# uController.net
KiCad netlist of a schematic drawn in Altium Designer
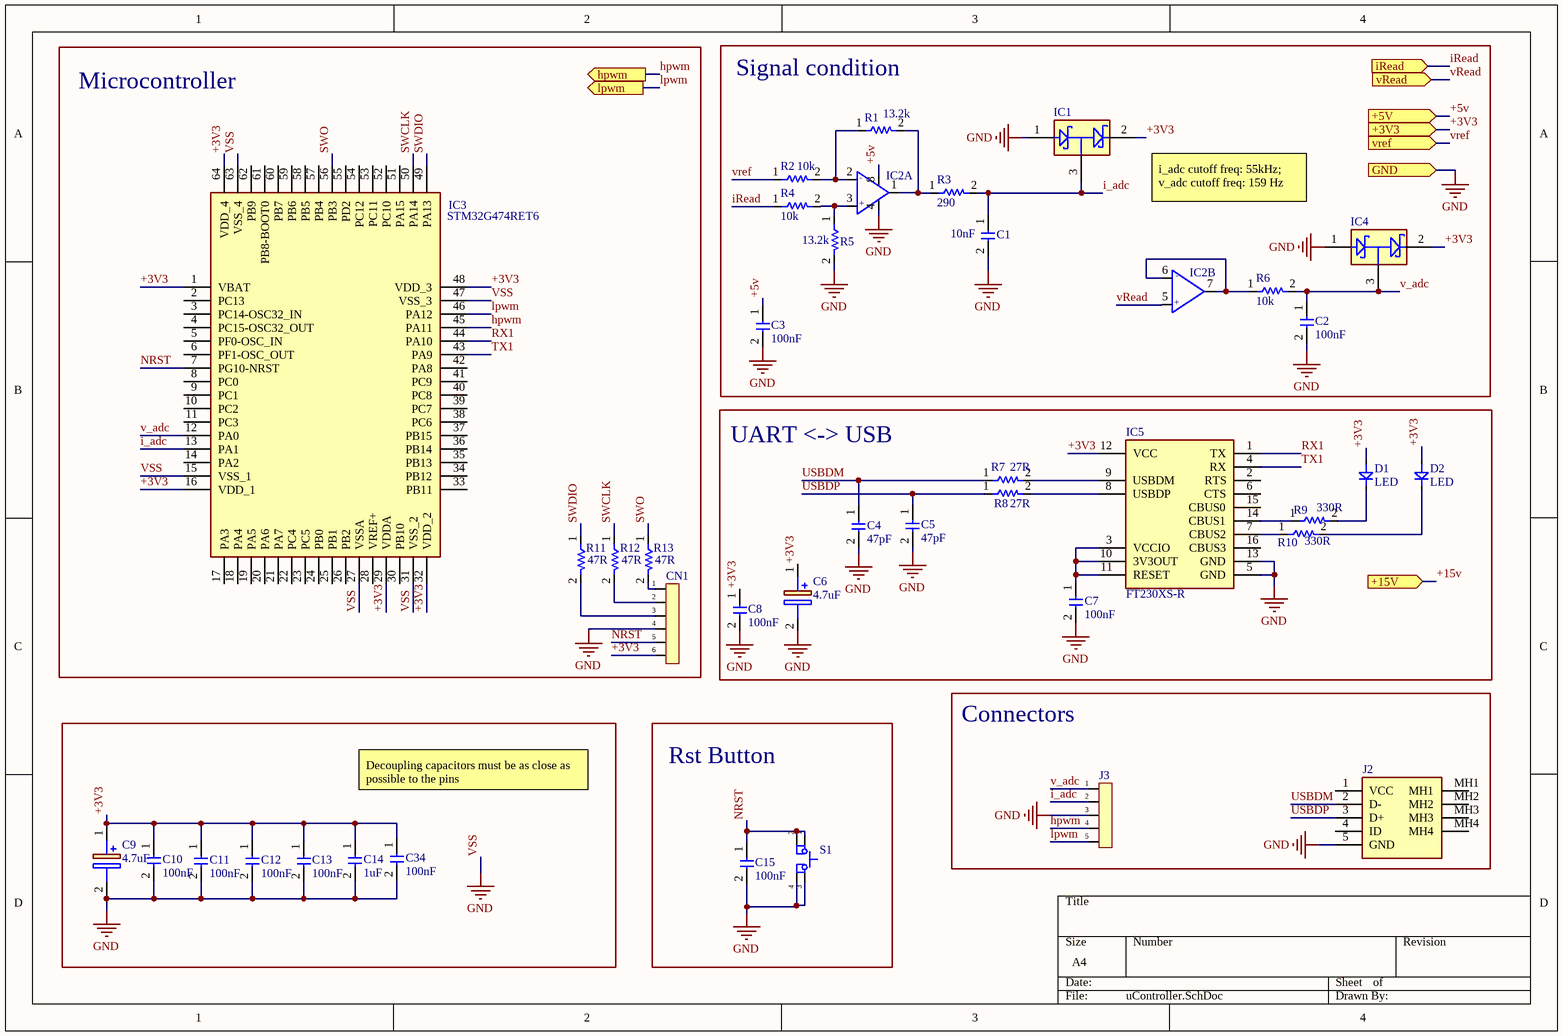
[diagram p0: uController.SchDoc]

(export (version "E")
  (design (tool "Eeschema 10.0.6"))
  (components
    (comp (ref "C1")
      (value "10nF")
      (footprint "CAPACITOR_0805")
      (libsource (lib "Schlib1") (part "Capacitor"))
    )
    (comp (ref "C2")
      (value "100nF")
      (footprint "CAPACITOR_0805")
      (libsource (lib "Schlib1") (part "Capacitor"))
    )
    (comp (ref "C3")
      (value "100nF")
      (footprint "CAPACITOR_0805")
      (libsource (lib "Schlib1") (part "Capacitor"))
    )
    (comp (ref "C4")
      (value "47pF")
      (footprint "CAPACITOR_0805")
      (libsource (lib "Schlib1") (part "Capacitor"))
    )
    (comp (ref "C5")
      (value "47pF")
      (footprint "CAPACITOR_0805")
      (libsource (lib "Schlib1") (part "Capacitor"))
    )
    (comp (ref "C6")
      (value "4.7uF")
      (footprint "Capacitor 0805 polaryzed")
      (libsource (lib "Schlib1") (part "Capacitor polaryzed"))
    )
    (comp (ref "C7")
      (value "100nF")
      (footprint "CAPACITOR_0805")
      (libsource (lib "Schlib1") (part "Capacitor"))
    )
    (comp (ref "C8")
      (value "100nF")
      (footprint "CAPACITOR_0805")
      (libsource (lib "Schlib1") (part "Capacitor"))
    )
    (comp (ref "C9")
      (value "4.7uF")
      (footprint "Capacitor 0805 polaryzed")
      (libsource (lib "Schlib1") (part "Capacitor polaryzed"))
    )
    (comp (ref "C10")
      (value "100nF")
      (footprint "CAPACITOR_0805")
      (libsource (lib "Schlib1") (part "Capacitor"))
    )
    (comp (ref "C11")
      (value "100nF")
      (footprint "CAPACITOR_0805")
      (libsource (lib "Schlib1") (part "Capacitor"))
    )
    (comp (ref "C12")
      (value "100nF")
      (footprint "CAPACITOR_0805")
      (libsource (lib "Schlib1") (part "Capacitor"))
    )
    (comp (ref "C13")
      (value "100nF")
      (footprint "CAPACITOR_0805")
      (libsource (lib "Schlib1") (part "Capacitor"))
    )
    (comp (ref "C14")
      (value "1uF")
      (footprint "CAPACITOR_0805")
      (libsource (lib "Schlib1") (part "Capacitor"))
    )
    (comp (ref "C15")
      (value "100nF")
      (footprint "CAPACITOR_0805")
      (libsource (lib "Schlib1") (part "Capacitor"))
    )
    (comp (ref "C34")
      (value "100nF")
      (footprint "CAPACITOR_0805")
      (libsource (lib "Schlib1") (part "Capacitor"))
    )
    (comp (ref "CN1")
      (value "Conector 1x6P")
      (footprint "Header 2x3")
      (libsource (lib "Schlib1") (part "Conector 1x6P"))
    )
    (comp (ref "D1") (value "LED") (footprint "LED 0805") (libsource (lib "Schlib1") (part "LED")))
    (comp (ref "D2") (value "LED") (footprint "LED 0805") (libsource (lib "Schlib1") (part "LED")))
    (comp (ref "IC1") (value "bat54s") (footprint "BAT54S") (libsource (lib "Schlib1") (part "bat54s")))
    (comp (ref "IC2") (value "TSX712IDT") (footprint "SO-8") (libsource (lib "Schlib1") (part "TSX712IDT")))
    (comp (ref "IC3")
      (value "STM32G474RET6")
      (footprint "QFP50P1200X1200X160-64N")
      (description "Integrated Circuit")
      (fields (field (name "MOUSER PART NUMBER") "511-STM32G474RET6"))
      (libsource (lib "*") (part "STM32G474RET6"))
    )
    (comp (ref "IC4") (value "bat54s") (footprint "BAT54S") (libsource (lib "Schlib1") (part "bat54s")))
    (comp (ref "IC5")
      (value "FT230XS-R")
      (footprint "SSOP-16")
      (libsource (lib "Schlib1") (part "FT230XS-R"))
    )
    (comp (ref "J2")
      (value "UJ2-MIBH2-4-SMT-TR")
      (footprint "UJ2MIBH24SMTTR")
      (description "Connector")
      (fields (field (name "MOUSER PART NUMBER") "490-UJ2-MIBH2-4-SMT"))
      (libsource (lib "Schlib1") (part "UJ2-MIBH2-4-SMT-TR"))
    )
    (comp (ref "J3")
      (value "Conector 1x5P")
      (footprint "HEADER 1X5")
      (libsource (lib "Schlib1") (part "Conector 1x5P"))
    )
    (comp (ref "R1")
      (value "13.2k")
      (footprint "RESISTOR_0805")
      (libsource (lib "Schlib1") (part "Resistor"))
    )
    (comp (ref "R2") (value "10k") (footprint "RESISTOR_0805") (libsource (lib "Schlib1") (part "Resistor")))
    (comp (ref "R3") (value "290") (footprint "RESISTOR_0805") (libsource (lib "Schlib1") (part "Resistor")))
    (comp (ref "R4") (value "10k") (footprint "RESISTOR_0805") (libsource (lib "Schlib1") (part "Resistor")))
    (comp (ref "R5")
      (value "13.2k")
      (footprint "RESISTOR_0805")
      (libsource (lib "Schlib1") (part "Resistor"))
    )
    (comp (ref "R6") (value "10k") (footprint "RESISTOR_0805") (libsource (lib "Schlib1") (part "Resistor")))
    (comp (ref "R7") (value "27R") (footprint "RESISTOR_0805") (libsource (lib "Schlib1") (part "Resistor")))
    (comp (ref "R8") (value "27R") (footprint "RESISTOR_0805") (libsource (lib "Schlib1") (part "Resistor")))
    (comp (ref "R9") (value "330R") (footprint "RESISTOR_0805") (libsource (lib "Schlib1") (part "Resistor")))
    (comp (ref "R10")
      (value "330R")
      (footprint "RESISTOR_0805")
      (libsource (lib "Schlib1") (part "Resistor"))
    )
    (comp (ref "R11") (value "47R") (footprint "RESISTOR_0805") (libsource (lib "Schlib1") (part "Resistor")))
    (comp (ref "R12") (value "47R") (footprint "RESISTOR_0805") (libsource (lib "Schlib1") (part "Resistor")))
    (comp (ref "R13") (value "47R") (footprint "RESISTOR_0805") (libsource (lib "Schlib1") (part "Resistor")))
    (comp (ref "S1")
      (value "pushButton")
      (footprint "Push_Button")
      (libsource (lib "Schlib1") (part "pushButton"))
    )
  )
  (nets
    (net (code "1") (name "/+3V3") (class "Default")
      (node (ref "C10") (pin "1") (pinfunction "1_1") (pintype "passive"))
      (node (ref "C11") (pin "1") (pinfunction "1_1") (pintype "passive"))
      (node (ref "C12") (pin "1") (pinfunction "1_1") (pintype "passive"))
      (node (ref "C13") (pin "1") (pinfunction "1_1") (pintype "passive"))
      (node (ref "C14") (pin "1") (pinfunction "1_1") (pintype "passive"))
      (node (ref "C34") (pin "1") (pinfunction "1_1") (pintype "passive"))
      (node (ref "C6") (pin "1") (pinfunction "+_1") (pintype "passive"))
      (node (ref "C8") (pin "1") (pinfunction "1_1") (pintype "passive"))
      (node (ref "C9") (pin "1") (pinfunction "+_1") (pintype "passive"))
      (node (ref "CN1") (pin "6") (pinfunction "6_6") (pintype "passive"))
      (node (ref "D1") (pin "2") (pinfunction "12_2") (pintype "passive"))
      (node (ref "D2") (pin "2") (pinfunction "12_2") (pintype "passive"))
      (node (ref "IC1") (pin "2") (pinfunction "OUT_2") (pintype "passive"))
      (node (ref "IC3") (pin "1") (pinfunction "VBAT_1") (pintype "passive"))
      (node (ref "IC3") (pin "16") (pinfunction "VDD_1_16") (pintype "passive"))
      (node (ref "IC3") (pin "29") (pinfunction "VDDA_29") (pintype "passive"))
      (node (ref "IC3") (pin "32") (pinfunction "VDD_2_32") (pintype "passive"))
      (node (ref "IC3") (pin "48") (pinfunction "VDD_3_48") (pintype "passive"))
      (node (ref "IC3") (pin "64") (pinfunction "VDD_4_64") (pintype "passive"))
      (node (ref "IC4") (pin "2") (pinfunction "OUT_2") (pintype "passive"))
      (node (ref "IC5") (pin "12") (pinfunction "VCC_12") (pintype "passive"))
    )
    (net (code "3") (name "/+5v") (class "Default")
      (node (ref "C3") (pin "1") (pinfunction "1_1") (pintype "passive"))
      (node (ref "IC2") (pin "8") (pinfunction "8_8") (pintype "passive"))
    )
    (net (code "5") (name "/NRST") (class "Default")
      (node (ref "C15") (pin "1") (pinfunction "1_1") (pintype "passive"))
      (node (ref "CN1") (pin "5") (pinfunction "5_5") (pintype "passive"))
      (node (ref "IC3") (pin "7") (pinfunction "PG10-NRST_7") (pintype "passive"))
      (node (ref "S1") (pin "1") (pinfunction "1_1") (pintype "passive"))
      (node (ref "S1") (pin "2") (pinfunction "2_2") (pintype "passive"))
    )
    (net (code "6") (name "/RX1") (class "Default")
      (node (ref "IC3") (pin "44") (pinfunction "PA10_44") (pintype "passive"))
      (node (ref "IC5") (pin "1") (pinfunction "TX_1") (pintype "passive"))
    )
    (net (code "7") (name "/SWCLK") (class "Default")
      (node (ref "IC3") (pin "50") (pinfunction "PA14_50") (pintype "passive"))
      (node (ref "R12") (pin "1") (pinfunction "6_1") (pintype "passive"))
    )
    (net (code "8") (name "/SWDIO") (class "Default")
      (node (ref "IC3") (pin "49") (pinfunction "PA13_49") (pintype "passive"))
      (node (ref "R11") (pin "1") (pinfunction "6_1") (pintype "passive"))
    )
    (net (code "9") (name "/SWO") (class "Default")
      (node (ref "IC3") (pin "56") (pinfunction "PB3_56") (pintype "passive"))
      (node (ref "R13") (pin "1") (pinfunction "6_1") (pintype "passive"))
    )
    (net (code "10") (name "/TX1") (class "Default")
      (node (ref "IC3") (pin "43") (pinfunction "PA9_43") (pintype "passive"))
      (node (ref "IC5") (pin "4") (pinfunction "RX_4") (pintype "passive"))
    )
    (net (code "11") (name "/USBDM") (class "Default")
      (node (ref "C4") (pin "1") (pinfunction "1_1") (pintype "passive"))
      (node (ref "J2") (pin "2") (pinfunction "D-_2") (pintype "passive"))
      (node (ref "R7") (pin "1") (pinfunction "6_1") (pintype "passive"))
    )
    (net (code "12") (name "/USBDP") (class "Default")
      (node (ref "C5") (pin "1") (pinfunction "1_1") (pintype "passive"))
      (node (ref "J2") (pin "3") (pinfunction "D+_3") (pintype "passive"))
      (node (ref "R8") (pin "1") (pinfunction "6_1") (pintype "passive"))
    )
    (net (code "13") (name "/hpwm") (class "Default")
      (node (ref "IC3") (pin "45") (pinfunction "PA11_45") (pintype "passive"))
      (node (ref "J3") (pin "4") (pinfunction "4_4") (pintype "passive"))
    )
    (net (code "14") (name "/iRead") (class "Default")
      (node (ref "R4") (pin "1") (pinfunction "6_1") (pintype "passive"))
    )
    (net (code "15") (name "/i_adc") (class "Default")
      (node (ref "C1") (pin "1") (pinfunction "1_1") (pintype "passive"))
      (node (ref "IC1") (pin "3") (pinfunction "COM_3") (pintype "passive"))
      (node (ref "IC3") (pin "13") (pinfunction "PA1_13") (pintype "passive"))
      (node (ref "J3") (pin "2") (pinfunction "2_2") (pintype "passive"))
      (node (ref "R3") (pin "2") (pinfunction "2_2") (pintype "passive"))
    )
    (net (code "16") (name "/lpwm") (class "Default")
      (node (ref "IC3") (pin "46") (pinfunction "PA12_46") (pintype "passive"))
      (node (ref "J3") (pin "5") (pinfunction "5_5") (pintype "passive"))
    )
    (net (code "17") (name "/vRead") (class "Default")
      (node (ref "IC2") (pin "5") (pinfunction "5_5") (pintype "passive"))
    )
    (net (code "18") (name "/v_adc") (class "Default")
      (node (ref "C2") (pin "1") (pinfunction "1_1") (pintype "passive"))
      (node (ref "IC3") (pin "12") (pinfunction "PA0_12") (pintype "passive"))
      (node (ref "IC4") (pin "3") (pinfunction "COM_3") (pintype "passive"))
      (node (ref "J3") (pin "1") (pinfunction "1_1") (pintype "passive"))
      (node (ref "R6") (pin "2") (pinfunction "2_2") (pintype "passive"))
    )
    (net (code "19") (name "/vref") (class "Default")
      (node (ref "R2") (pin "1") (pinfunction "6_1") (pintype "passive"))
    )
    (net (code "20") (name "GND") (class "Default")
      (node (ref "C1") (pin "2") (pinfunction "2_2") (pintype "passive"))
      (node (ref "C10") (pin "2") (pinfunction "2_2") (pintype "passive"))
      (node (ref "C11") (pin "2") (pinfunction "2_2") (pintype "passive"))
      (node (ref "C12") (pin "2") (pinfunction "2_2") (pintype "passive"))
      (node (ref "C13") (pin "2") (pinfunction "2_2") (pintype "passive"))
      (node (ref "C14") (pin "2") (pinfunction "2_2") (pintype "passive"))
      (node (ref "C15") (pin "2") (pinfunction "2_2") (pintype "passive"))
      (node (ref "C2") (pin "2") (pinfunction "2_2") (pintype "passive"))
      (node (ref "C3") (pin "2") (pinfunction "2_2") (pintype "passive"))
      (node (ref "C34") (pin "2") (pinfunction "2_2") (pintype "passive"))
      (node (ref "C4") (pin "2") (pinfunction "2_2") (pintype "passive"))
      (node (ref "C5") (pin "2") (pinfunction "2_2") (pintype "passive"))
      (node (ref "C6") (pin "2") (pinfunction "-_2") (pintype "passive"))
      (node (ref "C7") (pin "2") (pinfunction "2_2") (pintype "passive"))
      (node (ref "C8") (pin "2") (pinfunction "2_2") (pintype "passive"))
      (node (ref "C9") (pin "2") (pinfunction "-_2") (pintype "passive"))
      (node (ref "CN1") (pin "4") (pinfunction "4_4") (pintype "passive"))
      (node (ref "IC1") (pin "1") (pinfunction "IN_1") (pintype "passive"))
      (node (ref "IC2") (pin "4") (pinfunction "4_4") (pintype "passive"))
      (node (ref "IC3") (pin "15") (pinfunction "VSS_1_15") (pintype "passive"))
      (node (ref "IC3") (pin "27") (pinfunction "VSSA_27") (pintype "passive"))
      (node (ref "IC3") (pin "31") (pinfunction "VSS_2_31") (pintype "passive"))
      (node (ref "IC3") (pin "47") (pinfunction "VSS_3_47") (pintype "passive"))
      (node (ref "IC3") (pin "63") (pinfunction "VSS_4_63") (pintype "passive"))
      (node (ref "IC4") (pin "1") (pinfunction "IN_1") (pintype "passive"))
      (node (ref "IC5") (pin "13") (pinfunction "GND_13") (pintype "passive"))
      (node (ref "IC5") (pin "5") (pinfunction "GND_5") (pintype "passive"))
      (node (ref "J2") (pin "5") (pinfunction "GND_5") (pintype "passive"))
      (node (ref "J3") (pin "3") (pinfunction "3_3") (pintype "passive"))
      (node (ref "R5") (pin "2") (pinfunction "2_2") (pintype "passive"))
      (node (ref "S1") (pin "3") (pinfunction "3_3") (pintype "passive"))
      (node (ref "S1") (pin "4") (pinfunction "4_4") (pintype "passive"))
    )
    (net (code "21") (name "Net-(CN1-Pad1)") (class "Default")
      (node (ref "CN1") (pin "1") (pinfunction "1_1") (pintype "passive"))
      (node (ref "R13") (pin "2") (pinfunction "2_2") (pintype "passive"))
    )
    (net (code "22") (name "Net-(CN1-Pad2)") (class "Default")
      (node (ref "CN1") (pin "2") (pinfunction "2_2") (pintype "passive"))
      (node (ref "R12") (pin "2") (pinfunction "2_2") (pintype "passive"))
    )
    (net (code "23") (name "Net-(CN1-Pad3)") (class "Default")
      (node (ref "CN1") (pin "3") (pinfunction "3_3") (pintype "passive"))
      (node (ref "R11") (pin "2") (pinfunction "2_2") (pintype "passive"))
    )
    (net (code "24") (name "Net-(D1-11)") (class "Default")
      (node (ref "D1") (pin "1") (pinfunction "11_1") (pintype "passive"))
      (node (ref "R9") (pin "2") (pinfunction "2_2") (pintype "passive"))
    )
    (net (code "25") (name "Net-(D2-11)") (class "Default")
      (node (ref "D2") (pin "1") (pinfunction "11_1") (pintype "passive"))
      (node (ref "R10") (pin "2") (pinfunction "2_2") (pintype "passive"))
    )
    (net (code "26") (name "Net-(IC5-3V3OUT)") (class "Default")
      (node (ref "C7") (pin "1") (pinfunction "1_1") (pintype "passive"))
      (node (ref "IC5") (pin "10") (pinfunction "3V3OUT_10") (pintype "passive"))
      (node (ref "IC5") (pin "11") (pinfunction "RESET_11") (pintype "passive"))
      (node (ref "IC5") (pin "3") (pinfunction "VCCIO_3") (pintype "passive"))
    )
    (net (code "27") (name "Net-(IC5-CBUS1)") (class "Default")
      (node (ref "IC5") (pin "14") (pinfunction "CBUS1_14") (pintype "passive"))
      (node (ref "R9") (pin "1") (pinfunction "6_1") (pintype "passive"))
    )
    (net (code "28") (name "Net-(IC5-CBUS2)") (class "Default")
      (node (ref "IC5") (pin "7") (pinfunction "CBUS2_7") (pintype "passive"))
      (node (ref "R10") (pin "1") (pinfunction "6_1") (pintype "passive"))
    )
    (net (code "29") (name "Net-(IC5-USBDM)") (class "Default")
      (node (ref "IC5") (pin "9") (pinfunction "USBDM_9") (pintype "passive"))
      (node (ref "R7") (pin "2") (pinfunction "2_2") (pintype "passive"))
    )
    (net (code "30") (name "Net-(IC5-USBDP)") (class "Default")
      (node (ref "IC5") (pin "8") (pinfunction "USBDP_8") (pintype "passive"))
      (node (ref "R8") (pin "2") (pinfunction "2_2") (pintype "passive"))
    )
    (net (code "31") (name "Net-(R1-6)") (class "Default")
      (node (ref "IC2") (pin "2") (pinfunction "2_2") (pintype "passive"))
      (node (ref "R1") (pin "1") (pinfunction "6_1") (pintype "passive"))
      (node (ref "R2") (pin "2") (pinfunction "2_2") (pintype "passive"))
    )
    (net (code "32") (name "Net-(R3-6)") (class "Default")
      (node (ref "IC2") (pin "1") (pinfunction "1_1") (pintype "passive"))
      (node (ref "R1") (pin "2") (pinfunction "2_2") (pintype "passive"))
      (node (ref "R3") (pin "1") (pinfunction "6_1") (pintype "passive"))
    )
    (net (code "33") (name "Net-(R5-6)") (class "Default")
      (node (ref "IC2") (pin "3") (pinfunction "3_3") (pintype "passive"))
      (node (ref "R4") (pin "2") (pinfunction "2_2") (pintype "passive"))
      (node (ref "R5") (pin "1") (pinfunction "6_1") (pintype "passive"))
    )
    (net (code "34") (name "Net-(R6-6)") (class "Default")
      (node (ref "IC2") (pin "6") (pinfunction "6_6") (pintype "passive"))
      (node (ref "IC2") (pin "7") (pinfunction "7_7") (pintype "passive"))
      (node (ref "R6") (pin "1") (pinfunction "6_1") (pintype "passive"))
    )
    (net (code "35") (name "unconnected-(IC3-PA2-Pad14)") (class "Default")
      (node (ref "IC3") (pin "14") (pinfunction "PA2_14") (pintype "passive"))
    )
    (net (code "36") (name "unconnected-(IC3-PA3-Pad17)") (class "Default")
      (node (ref "IC3") (pin "17") (pinfunction "PA3_17") (pintype "passive"))
    )
    (net (code "37") (name "unconnected-(IC3-PA4-Pad18)") (class "Default")
      (node (ref "IC3") (pin "18") (pinfunction "PA4_18") (pintype "passive"))
    )
    (net (code "38") (name "unconnected-(IC3-PA5-Pad19)") (class "Default")
      (node (ref "IC3") (pin "19") (pinfunction "PA5_19") (pintype "passive"))
    )
    (net (code "39") (name "unconnected-(IC3-PA6-Pad20)") (class "Default")
      (node (ref "IC3") (pin "20") (pinfunction "PA6_20") (pintype "passive"))
    )
    (net (code "40") (name "unconnected-(IC3-PA7-Pad21)") (class "Default")
      (node (ref "IC3") (pin "21") (pinfunction "PA7_21") (pintype "passive"))
    )
    (net (code "41") (name "unconnected-(IC3-PA8-Pad42)") (class "Default")
      (node (ref "IC3") (pin "42") (pinfunction "PA8_42") (pintype "passive"))
    )
    (net (code "42") (name "unconnected-(IC3-PA15-Pad51)") (class "Default")
      (node (ref "IC3") (pin "51") (pinfunction "PA15_51") (pintype "passive"))
    )
    (net (code "43") (name "unconnected-(IC3-PB0-Pad24)") (class "Default")
      (node (ref "IC3") (pin "24") (pinfunction "PB0_24") (pintype "passive"))
    )
    (net (code "44") (name "unconnected-(IC3-PB1-Pad25)") (class "Default")
      (node (ref "IC3") (pin "25") (pinfunction "PB1_25") (pintype "passive"))
    )
    (net (code "45") (name "unconnected-(IC3-PB2-Pad26)") (class "Default")
      (node (ref "IC3") (pin "26") (pinfunction "PB2_26") (pintype "passive"))
    )
    (net (code "46") (name "unconnected-(IC3-PB4-Pad57)") (class "Default")
      (node (ref "IC3") (pin "57") (pinfunction "PB4_57") (pintype "passive"))
    )
    (net (code "47") (name "unconnected-(IC3-PB5-Pad58)") (class "Default")
      (node (ref "IC3") (pin "58") (pinfunction "PB5_58") (pintype "passive"))
    )
    (net (code "48") (name "unconnected-(IC3-PB6-Pad59)") (class "Default")
      (node (ref "IC3") (pin "59") (pinfunction "PB6_59") (pintype "passive"))
    )
    (net (code "49") (name "unconnected-(IC3-PB7-Pad60)") (class "Default")
      (node (ref "IC3") (pin "60") (pinfunction "PB7_60") (pintype "passive"))
    )
    (net (code "50") (name "unconnected-(IC3-PB8-BOOT0-Pad61)") (class "Default")
      (node (ref "IC3") (pin "61") (pinfunction "PB8-BOOT0_61") (pintype "passive"))
    )
    (net (code "51") (name "unconnected-(IC3-PB9-Pad62)") (class "Default")
      (node (ref "IC3") (pin "62") (pinfunction "PB9_62") (pintype "passive"))
    )
    (net (code "52") (name "unconnected-(IC3-PB10-Pad30)") (class "Default")
      (node (ref "IC3") (pin "30") (pinfunction "PB10_30") (pintype "passive"))
    )
    (net (code "53") (name "unconnected-(IC3-PB11-Pad33)") (class "Default")
      (node (ref "IC3") (pin "33") (pinfunction "PB11_33") (pintype "passive"))
    )
    (net (code "54") (name "unconnected-(IC3-PB12-Pad34)") (class "Default")
      (node (ref "IC3") (pin "34") (pinfunction "PB12_34") (pintype "passive"))
    )
    (net (code "55") (name "unconnected-(IC3-PB13-Pad35)") (class "Default")
      (node (ref "IC3") (pin "35") (pinfunction "PB13_35") (pintype "passive"))
    )
    (net (code "56") (name "unconnected-(IC3-PB14-Pad36)") (class "Default")
      (node (ref "IC3") (pin "36") (pinfunction "PB14_36") (pintype "passive"))
    )
    (net (code "57") (name "unconnected-(IC3-PB15-Pad37)") (class "Default")
      (node (ref "IC3") (pin "37") (pinfunction "PB15_37") (pintype "passive"))
    )
    (net (code "58") (name "unconnected-(IC3-PC0-Pad8)") (class "Default")
      (node (ref "IC3") (pin "8") (pinfunction "PC0_8") (pintype "passive"))
    )
    (net (code "59") (name "unconnected-(IC3-PC1-Pad9)") (class "Default")
      (node (ref "IC3") (pin "9") (pinfunction "PC1_9") (pintype "passive"))
    )
    (net (code "60") (name "unconnected-(IC3-PC2-Pad10)") (class "Default")
      (node (ref "IC3") (pin "10") (pinfunction "PC2_10") (pintype "passive"))
    )
    (net (code "61") (name "unconnected-(IC3-PC3-Pad11)") (class "Default")
      (node (ref "IC3") (pin "11") (pinfunction "PC3_11") (pintype "passive"))
    )
    (net (code "62") (name "unconnected-(IC3-PC4-Pad22)") (class "Default")
      (node (ref "IC3") (pin "22") (pinfunction "PC4_22") (pintype "passive"))
    )
    (net (code "63") (name "unconnected-(IC3-PC5-Pad23)") (class "Default")
      (node (ref "IC3") (pin "23") (pinfunction "PC5_23") (pintype "passive"))
    )
    (net (code "64") (name "unconnected-(IC3-PC6-Pad38)") (class "Default")
      (node (ref "IC3") (pin "38") (pinfunction "PC6_38") (pintype "passive"))
    )
    (net (code "65") (name "unconnected-(IC3-PC7-Pad39)") (class "Default")
      (node (ref "IC3") (pin "39") (pinfunction "PC7_39") (pintype "passive"))
    )
    (net (code "66") (name "unconnected-(IC3-PC8-Pad40)") (class "Default")
      (node (ref "IC3") (pin "40") (pinfunction "PC8_40") (pintype "passive"))
    )
    (net (code "67") (name "unconnected-(IC3-PC9-Pad41)") (class "Default")
      (node (ref "IC3") (pin "41") (pinfunction "PC9_41") (pintype "passive"))
    )
    (net (code "68") (name "unconnected-(IC3-PC10-Pad52)") (class "Default")
      (node (ref "IC3") (pin "52") (pinfunction "PC10_52") (pintype "passive"))
    )
    (net (code "69") (name "unconnected-(IC3-PC11-Pad53)") (class "Default")
      (node (ref "IC3") (pin "53") (pinfunction "PC11_53") (pintype "passive"))
    )
    (net (code "70") (name "unconnected-(IC3-PC12-Pad54)") (class "Default")
      (node (ref "IC3") (pin "54") (pinfunction "PC12_54") (pintype "passive"))
    )
    (net (code "71") (name "unconnected-(IC3-PC13-Pad2)") (class "Default")
      (node (ref "IC3") (pin "2") (pinfunction "PC13_2") (pintype "passive"))
    )
    (net (code "72") (name "unconnected-(IC3-PC14-OSC32_IN-Pad3)") (class "Default")
      (node (ref "IC3") (pin "3") (pinfunction "PC14-OSC32_IN_3") (pintype "passive"))
    )
    (net (code "73") (name "unconnected-(IC3-PC15-OSC32_OUT-Pad4)") (class "Default")
      (node (ref "IC3") (pin "4") (pinfunction "PC15-OSC32_OUT_4") (pintype "passive"))
    )
    (net (code "74") (name "unconnected-(IC3-PD2-Pad55)") (class "Default")
      (node (ref "IC3") (pin "55") (pinfunction "PD2_55") (pintype "passive"))
    )
    (net (code "75") (name "unconnected-(IC3-PF0-OSC_IN-Pad5)") (class "Default")
      (node (ref "IC3") (pin "5") (pinfunction "PF0-OSC_IN_5") (pintype "passive"))
    )
    (net (code "76") (name "unconnected-(IC3-PF1-OSC_OUT-Pad6)") (class "Default")
      (node (ref "IC3") (pin "6") (pinfunction "PF1-OSC_OUT_6") (pintype "passive"))
    )
    (net (code "77") (name "unconnected-(IC3-VREF+-Pad28)") (class "Default")
      (node (ref "IC3") (pin "28") (pinfunction "VREF+_28") (pintype "passive"))
    )
    (net (code "78") (name "unconnected-(IC5-CBUS0-Pad15)") (class "Default")
      (node (ref "IC5") (pin "15") (pinfunction "CBUS0_15") (pintype "passive"))
    )
    (net (code "79") (name "unconnected-(IC5-CBUS3-Pad16)") (class "Default")
      (node (ref "IC5") (pin "16") (pinfunction "CBUS3_16") (pintype "passive"))
    )
    (net (code "80") (name "unconnected-(IC5-CTS-Pad6)") (class "Default")
      (node (ref "IC5") (pin "6") (pinfunction "CTS_6") (pintype "passive"))
    )
    (net (code "81") (name "unconnected-(IC5-RTS-Pad2)") (class "Default")
      (node (ref "IC5") (pin "2") (pinfunction "RTS_2") (pintype "passive"))
    )
    (net (code "82") (name "unconnected-(J2-ID-Pad4)") (class "Default")
      (node (ref "J2") (pin "4") (pinfunction "ID_4") (pintype "passive"))
    )
    (net (code "83") (name "unconnected-(J2-PadMH1)") (class "Default")
      (node (ref "J2") (pin "MH1") (pinfunction "MH1_MH1") (pintype "passive"))
    )
    (net (code "84") (name "unconnected-(J2-PadMH2)") (class "Default")
      (node (ref "J2") (pin "MH2") (pinfunction "MH2_MH2") (pintype "passive"))
    )
    (net (code "85") (name "unconnected-(J2-PadMH3)") (class "Default")
      (node (ref "J2") (pin "MH3") (pinfunction "MH3_MH3") (pintype "passive"))
    )
    (net (code "86") (name "unconnected-(J2-PadMH4)") (class "Default")
      (node (ref "J2") (pin "MH4") (pinfunction "MH4_MH4") (pintype "passive"))
    )
    (net (code "87") (name "unconnected-(J2-VCC-Pad1)") (class "Default")
      (node (ref "J2") (pin "1") (pinfunction "VCC_1") (pintype "passive"))
    )
  )
)
